# MCU.net
KiCad netlist of a schematic drawn in Altium Designer
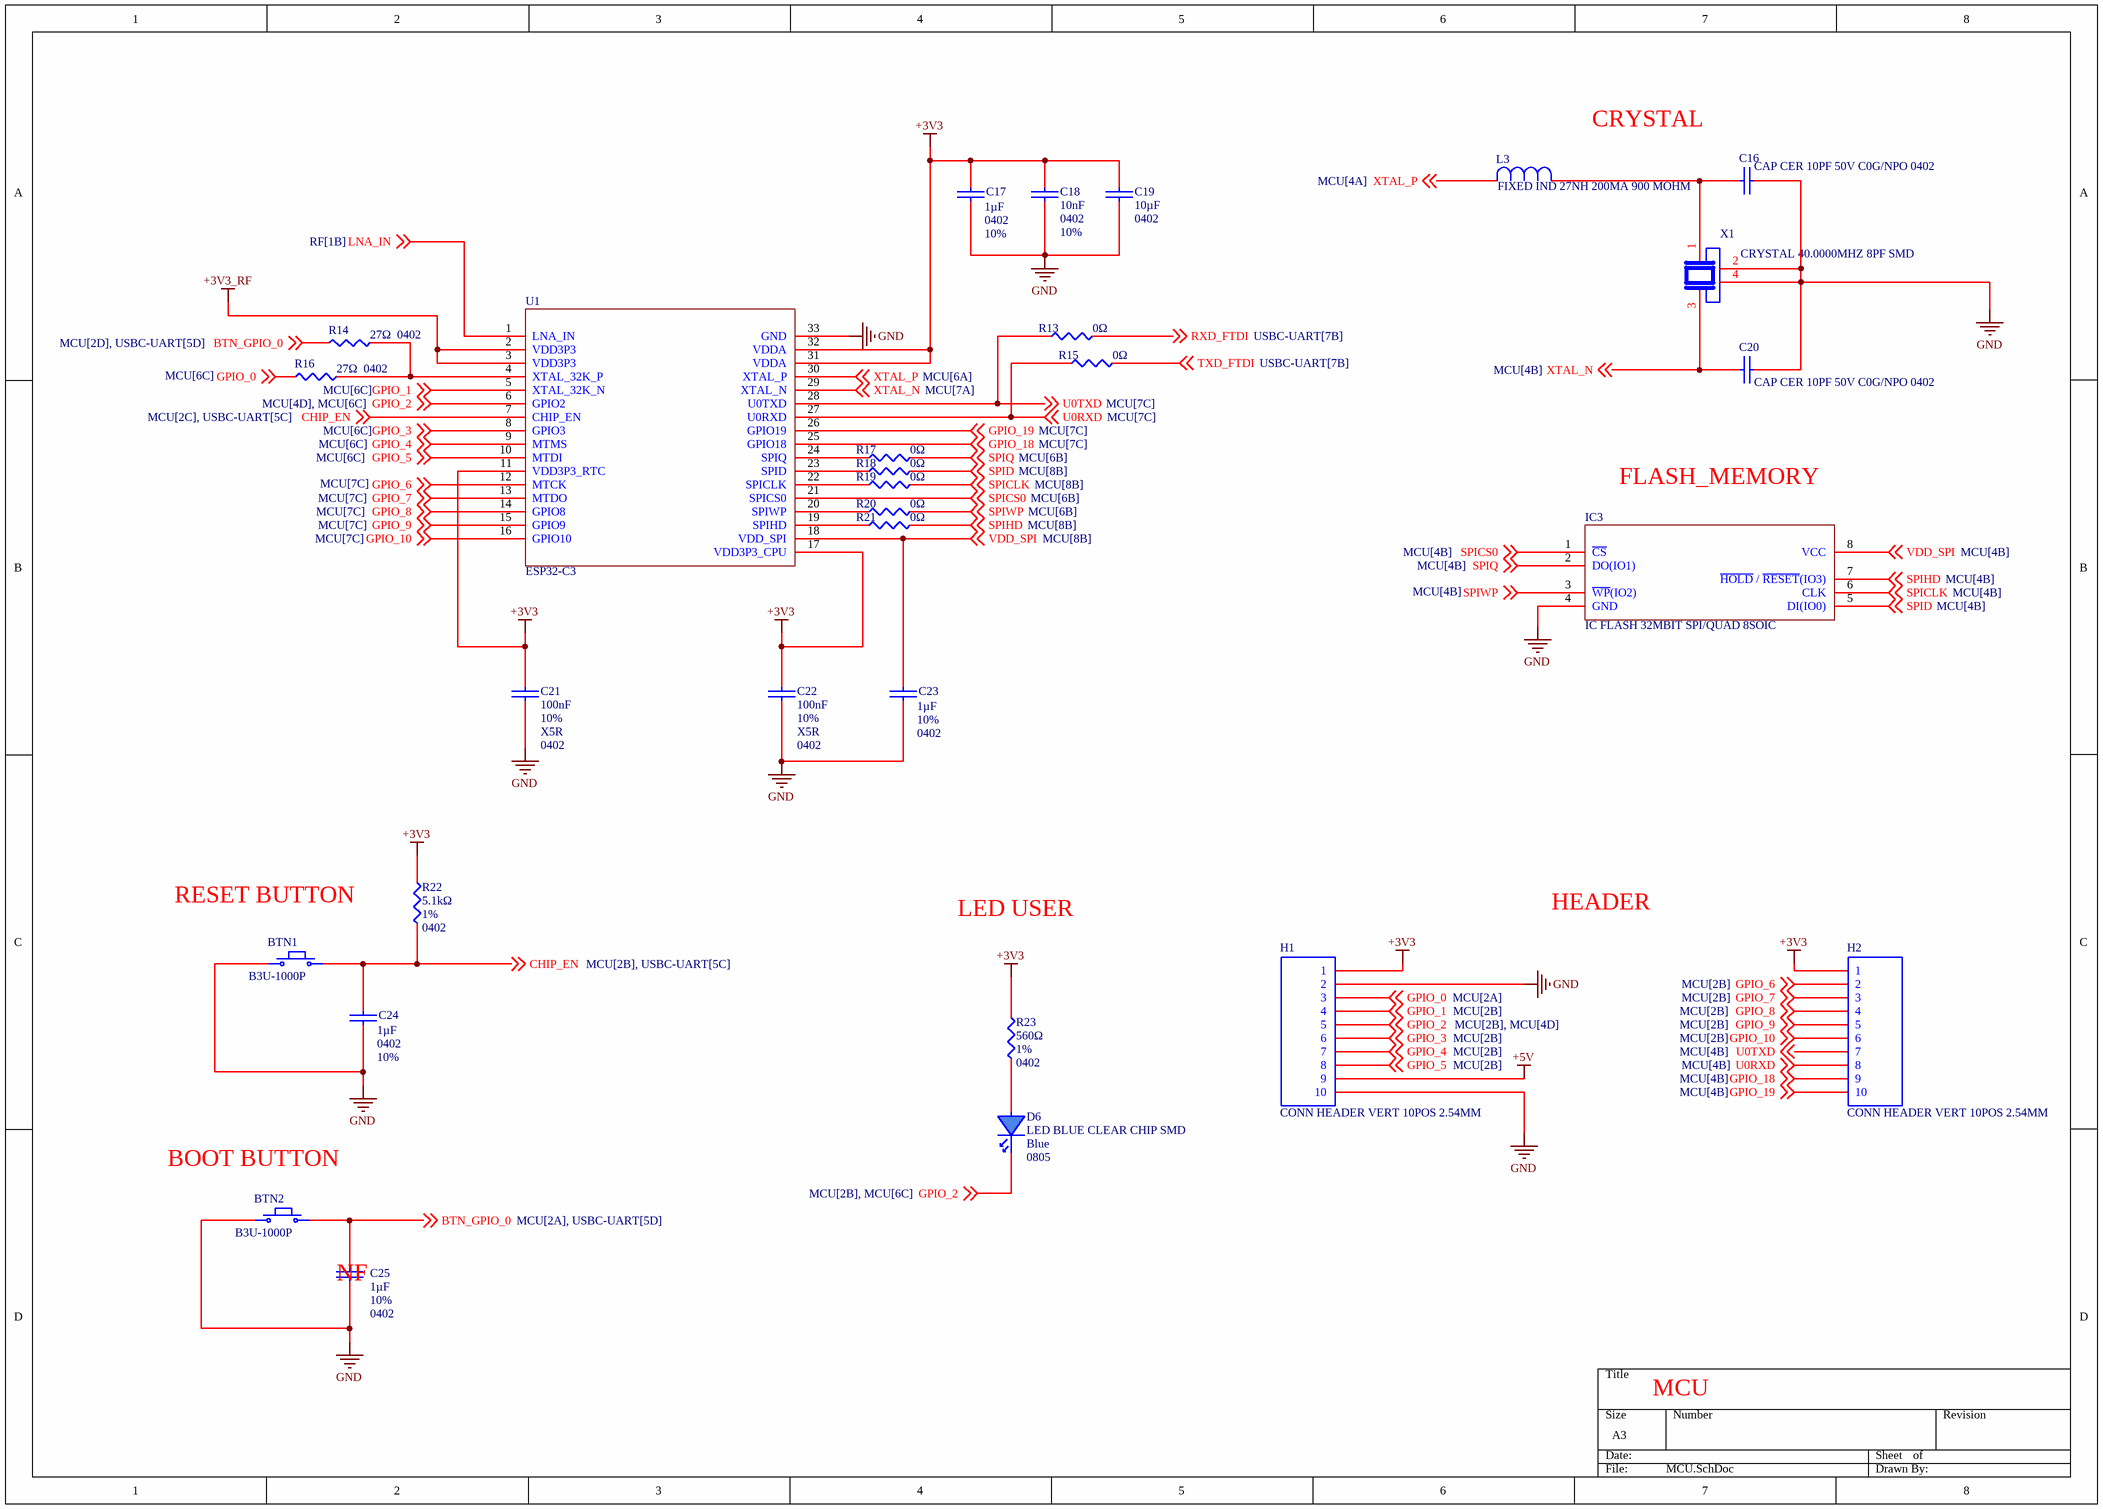
[diagram p0: MCU.SchDoc]

(export (version "E")
  (design (tool "Eeschema 10.0.6"))
  (components
    (comp (ref "BTN1")
      (value "SWITCH TACTILE SPST-NO 0.05A 12V")
      (footprint "SW_B3U-1000P")
      (description "Switch Tactile N.O. SPST Round Button Solder Tab 12VDC 200000Cycles 1.5N SMD Emboss T/R")
      (fields
        (field (name "MANUFACTURER") "Omron")
        (field (name "MANUFACTURER PART NUMBER") "B3U-1000P")
        (field (name "LCSC PART") "C231329")
      )
      (libsource (lib "Schlib") (part "B3U-1000P"))
    )
    (comp (ref "BTN2")
      (value "SWITCH TACTILE SPST-NO 0.05A 12V")
      (footprint "SW_B3U-1000P")
      (description "Switch Tactile N.O. SPST Round Button Solder Tab 12VDC 200000Cycles 1.5N SMD Emboss T/R")
      (fields
        (field (name "MANUFACTURER") "Omron")
        (field (name "MANUFACTURER PART NUMBER") "B3U-1000P")
        (field (name "LCSC PART") "C231329")
      )
      (libsource (lib "Schlib") (part "B3U-1000P"))
    )
    (comp (ref "C16")
      (value "CAP CER 10PF 50V C0G/NPO 0402")
      (footprint "C0402")
      (fields
        (field (name "MANUFACTURER") "Yageo Group")
        (field (name "MANUFACTURER PART NUMBER") "CC0402FPNPO9BN100")
        (field (name "LCSC PART") "C3896396")
      )
      (libsource (lib "Schlib") (part "CC0402FPNPO9BN100"))
    )
    (comp (ref "C17")
      (value "1µF")
      (footprint "C0402")
      (description "Multilayer Ceramic Capacitors MLCC – SMD/SMT; YAGEO; CC0402KRX5R6BB105; 1 µF; 0402; 10 V; 10 V")
      (fields
        (field (name "MANUFACTURER") "Yageo Group")
        (field (name "MANUFACTURER PART NUMBER") "CC0402KRX5R6BB105")
        (field (name "CASE/PACKAGE") "0402")
        (field (name "TOLERANCE") "10%")
      )
      (libsource (lib "Schlib") (part "CC0402KRX5R6BB105"))
    )
    (comp (ref "C18")
      (value "10nF")
      (footprint "C0402")
      (description "Multilayer Ceramic Capacitors MLCC - SMD/SMT 16V 0.01uF X7R 0402 10%")
      (fields
        (field (name "MANUFACTURER") "Yageo Group")
        (field (name "MANUFACTURER PART NUMBER") "CC0402KRX7R7BB103")
        (field (name "CASE/PACKAGE") "0402")
        (field (name "TOLERANCE") "10%")
      )
      (libsource (lib "Schlib") (part "CC0402KRX7R7BB103"))
    )
    (comp (ref "C19")
      (value "10µF")
      (footprint "C0402")
      (description "10V 10uF X5R ±20% 0402 Multilayer Ceramic Capacitors MLCC - SMD/SMT ROHS")
      (fields
        (field (name "MANUFACTURER") "Murata")
        (field (name "MANUFACTURER PART NUMBER") "GRM155R61A106ME11D")
        (field (name "CASE/PACKAGE") "0402")
      )
      (libsource (lib "Schlib") (part "GRM155R61A106ME11D"))
    )
    (comp (ref "C20")
      (value "CAP CER 10PF 50V C0G/NPO 0402")
      (footprint "C0402")
      (fields
        (field (name "MANUFACTURER") "Yageo Group")
        (field (name "MANUFACTURER PART NUMBER") "CC0402FPNPO9BN100")
        (field (name "LCSC PART") "C3896396")
      )
      (libsource (lib "Schlib") (part "CC0402FPNPO9BN100"))
    )
    (comp (ref "C21")
      (value "100nF")
      (footprint "C0402")
      (description "50V 100nF X5R ±10% 0402 Multilayer Ceramic Capacitors MLCC - SMD/SMT ROHS")
      (fields
        (field (name "MANUFACTURER") "Yageo Group")
        (field (name "MANUFACTURER PART NUMBER") "CC0402KRX5R9BB104")
        (field (name "TOLERANCE") "10%")
        (field (name "DIELECTRIC") "X5R")
        (field (name "CASE/PACKAGE") "0402")
      )
      (libsource (lib "Schlib") (part "CC0402KRX5R9BB104"))
    )
    (comp (ref "C22")
      (value "100nF")
      (footprint "C0402")
      (description "50V 100nF X5R ±10% 0402 Multilayer Ceramic Capacitors MLCC - SMD/SMT ROHS")
      (fields
        (field (name "MANUFACTURER") "Yageo Group")
        (field (name "MANUFACTURER PART NUMBER") "CC0402KRX5R9BB104")
        (field (name "TOLERANCE") "10%")
        (field (name "DIELECTRIC") "X5R")
        (field (name "CASE/PACKAGE") "0402")
      )
      (libsource (lib "Schlib") (part "CC0402KRX5R9BB104"))
    )
    (comp (ref "C23")
      (value "1µF")
      (footprint "C0402")
      (description "Multilayer Ceramic Capacitors MLCC – SMD/SMT; YAGEO; CC0402KRX5R6BB105; 1 µF; 0402; 10 V; 10 V")
      (fields
        (field (name "MANUFACTURER") "Yageo Group")
        (field (name "MANUFACTURER PART NUMBER") "CC0402KRX5R6BB105")
        (field (name "CASE/PACKAGE") "0402")
        (field (name "TOLERANCE") "10%")
      )
      (libsource (lib "Schlib") (part "CC0402KRX5R6BB105"))
    )
    (comp (ref "C24")
      (value "1µF")
      (footprint "C0402")
      (description "Multilayer Ceramic Capacitors MLCC – SMD/SMT; YAGEO; CC0402KRX5R6BB105; 1 µF; 0402; 10 V; 10 V")
      (fields
        (field (name "MANUFACTURER") "Yageo Group")
        (field (name "MANUFACTURER PART NUMBER") "CC0402KRX5R6BB105")
        (field (name "CASE/PACKAGE") "0402")
        (field (name "TOLERANCE") "10%")
      )
      (libsource (lib "Schlib") (part "CC0402KRX5R6BB105"))
    )
    (comp (ref "C25")
      (value "1µF")
      (footprint "C0402")
      (description "Multilayer Ceramic Capacitors MLCC – SMD/SMT; YAGEO; CC0402KRX5R6BB105; 1 µF; 0402; 10 V; 10 V")
      (fields
        (field (name "MANUFACTURER") "Yageo Group")
        (field (name "MANUFACTURER PART NUMBER") "CC0402KRX5R6BB105")
        (field (name "CASE/PACKAGE") "0402")
        (field (name "TOLERANCE") "10%")
      )
      (libsource (lib "Schlib") (part "CC0402KRX5R6BB105"))
    )
    (comp (ref "D6")
      (value "LED BLUE CLEAR CHIP SMD")
      (footprint "LED_0805_BLUE")
      (description "LED blue LED0805 wavelength 465~475nm light intensity 28~180mcd vertical sticker")
      (fields
        (field (name "MANUFACTURER") "Diodes Inc.")
        (field (name "MANUFACTURER PART NUMBER") "LTST-C171TBKT")
        (field (name "COLOR") "Blue")
        (field (name "CASE/PACKAGE") "0805")
      )
      (libsource (lib "Schlib") (part "LTST-C171TBKT"))
    )
    (comp (ref "H1")
      (value "CONN HEADER VERT 10POS 2.54MM")
      (footprint "Header 1*10 2.54mm")
      (description "Conn Unshrouded Header HDR 10 POS 2.54mm Solder ST Top Entry Thru-Hole Bag")
      (fields (field (name "MANUFACTURER") "Adam Tech") (field (name "MANUFACTURER PART NUMBER") "PH1-10-UA"))
      (libsource (lib "Schlib") (part "PH1-10-UA"))
    )
    (comp (ref "H2")
      (value "CONN HEADER VERT 10POS 2.54MM")
      (footprint "Header 1*10 2.54mm")
      (description "Conn Unshrouded Header HDR 10 POS 2.54mm Solder ST Top Entry Thru-Hole Bag")
      (fields (field (name "MANUFACTURER") "Adam Tech") (field (name "MANUFACTURER PART NUMBER") "PH1-10-UA"))
      (libsource (lib "Schlib") (part "PH1-10-UA"))
    )
    (comp (ref "IC3")
      (value "IC FLASH 32MBIT SPI/QUAD 8SOIC")
      (footprint "SOIC-8_5P28X5P28_WIN-L")
      (description "NOR Flash Serial (SPI, Dual SPI, Quad SPI) 3V/3.3V 32M-bit 4M x 8 6ns 8-Pin SOIC T/R")
      (fields
        (field (name "MANUFACTURER") "Winbond")
        (field (name "MANUFACTURER PART NUMBER") "W25Q32JVSSIQ TR")
      )
      (libsource (lib "Schlib") (part "W25Q32JVSSIQ TR"))
    )
    (comp (ref "L3")
      (value "FIXED IND 27NH 200MA 900 MOHM")
      (footprint "IND_L-0402_JOT-L")
      (description "General Purpose Inductor, 0.027uH, 5%, 1 Element, Ceramic-Core, SMD, 0402")
      (fields
        (field (name "MANUFACTURER") "Knowles")
        (field (name "MANUFACTURER PART NUMBER") "LRC0402CJ27NGV001T")
      )
      (libsource (lib "Schlib") (part "LRC0402CJ27NGV001T"))
    )
    (comp (ref "R13")
      (value "0Ω")
      (footprint "R0402")
      (description "GENERAL PURPOSE CHIP RESISTOR Metal Glaze/thick Film, 0.0625W, 0ohm, Surface Mount, 0402")
      (fields
        (field (name "MANUFACTURER") "Yageo Group")
        (field (name "MANUFACTURER PART NUMBER") "RC0402JR-070RL")
      )
      (libsource (lib "Schlib") (part "RC0402JR-070RL"))
    )
    (comp (ref "R14")
      (value "27Ω")
      (footprint "R0402")
      (description "62.5mW Thin Film Resistor ±50ppm/℃ ±1% 27Ω 0402 Chip Resistor - Surface Mount ROHS")
      (fields
        (field (name "MANUFACTURER") "Yageo Group")
        (field (name "MANUFACTURER PART NUMBER") "RT0402FRE0727RL")
        (field (name "CASE/PACKAGE") "0402")
      )
      (libsource (lib "Schlib") (part "RT0402FRE0727RL"))
    )
    (comp (ref "R15")
      (value "0Ω")
      (footprint "R0402")
      (description "GENERAL PURPOSE CHIP RESISTOR Metal Glaze/thick Film, 0.0625W, 0ohm, Surface Mount, 0402")
      (fields
        (field (name "MANUFACTURER") "Yageo Group")
        (field (name "MANUFACTURER PART NUMBER") "RC0402JR-070RL")
      )
      (libsource (lib "Schlib") (part "RC0402JR-070RL"))
    )
    (comp (ref "R16")
      (value "27Ω")
      (footprint "R0402")
      (description "62.5mW Thin Film Resistor ±50ppm/℃ ±1% 27Ω 0402 Chip Resistor - Surface Mount ROHS")
      (fields
        (field (name "MANUFACTURER") "Yageo Group")
        (field (name "MANUFACTURER PART NUMBER") "RT0402FRE0727RL")
        (field (name "CASE/PACKAGE") "0402")
      )
      (libsource (lib "Schlib") (part "RT0402FRE0727RL"))
    )
    (comp (ref "R17")
      (value "0Ω")
      (footprint "R0402")
      (description "GENERAL PURPOSE CHIP RESISTOR Metal Glaze/thick Film, 0.0625W, 0ohm, Surface Mount, 0402")
      (fields
        (field (name "MANUFACTURER") "Yageo Group")
        (field (name "MANUFACTURER PART NUMBER") "RC0402JR-070RL")
      )
      (libsource (lib "Schlib") (part "RC0402JR-070RL"))
    )
    (comp (ref "R18")
      (value "0Ω")
      (footprint "R0402")
      (description "GENERAL PURPOSE CHIP RESISTOR Metal Glaze/thick Film, 0.0625W, 0ohm, Surface Mount, 0402")
      (fields
        (field (name "MANUFACTURER") "Yageo Group")
        (field (name "MANUFACTURER PART NUMBER") "RC0402JR-070RL")
      )
      (libsource (lib "Schlib") (part "RC0402JR-070RL"))
    )
    (comp (ref "R19")
      (value "0Ω")
      (footprint "R0402")
      (description "GENERAL PURPOSE CHIP RESISTOR Metal Glaze/thick Film, 0.0625W, 0ohm, Surface Mount, 0402")
      (fields
        (field (name "MANUFACTURER") "Yageo Group")
        (field (name "MANUFACTURER PART NUMBER") "RC0402JR-070RL")
      )
      (libsource (lib "Schlib") (part "RC0402JR-070RL"))
    )
    (comp (ref "R20")
      (value "0Ω")
      (footprint "R0402")
      (description "GENERAL PURPOSE CHIP RESISTOR Metal Glaze/thick Film, 0.0625W, 0ohm, Surface Mount, 0402")
      (fields
        (field (name "MANUFACTURER") "Yageo Group")
        (field (name "MANUFACTURER PART NUMBER") "RC0402JR-070RL")
      )
      (libsource (lib "Schlib") (part "RC0402JR-070RL"))
    )
    (comp (ref "R21")
      (value "0Ω")
      (footprint "R0402")
      (description "GENERAL PURPOSE CHIP RESISTOR Metal Glaze/thick Film, 0.0625W, 0ohm, Surface Mount, 0402")
      (fields
        (field (name "MANUFACTURER") "Yageo Group")
        (field (name "MANUFACTURER PART NUMBER") "RC0402JR-070RL")
      )
      (libsource (lib "Schlib") (part "RC0402JR-070RL"))
    )
    (comp (ref "R22")
      (value "5.1kΩ")
      (footprint "R0402")
      (description "62.5mW Thick Film Resistors 50V ±100ppm/℃ ±1% 5.1kΩ 0402 Chip Resistor - Surface Mount ROHS")
      (fields
        (field (name "MANUFACTURER") "Yageo Group")
        (field (name "MANUFACTURER PART NUMBER") "RC0402FR-075K1L")
        (field (name "TOLERANCE") "1%")
        (field (name "CASE/PACKAGE") "0402")
      )
      (libsource (lib "Schlib") (part "RC0402FR-075K1L"))
    )
    (comp (ref "R23")
      (value "560Ω")
      (footprint "R0402")
      (description "RC Series 0402 0.063 W 560 Ohm ±1% ±100 ppm/°C SMT Thick Film Chip Resistor")
      (fields
        (field (name "MANUFACTURER") "Yageo Group")
        (field (name "MANUFACTURER PART NUMBER") "RC0402FR-13560RL")
        (field (name "TOLERANCE") "1%")
        (field (name "CASE/PACKAGE") "0402")
      )
      (libsource (lib "Schlib") (part "RC0402FR-13560RL"))
    )
    (comp (ref "U1")
      (value "ESP32-C3")
      (footprint "ESP-C3")
      (description "400KB 22 3V~3.6V RISC-V 160MHz QFN-32-EP(5x5) Microcontroller Units (MCUs/MPUs/SOCs) ROHS")
      (fields (field (name "MANUFACTURER") "Espressif Systems") (field (name "LCSC PART") "C2838500"))
      (libsource (lib "Schlib") (part "ESP32-C3"))
    )
    (comp (ref "X1")
      (value "CRYSTAL 40.0000MHZ 8PF SMD")
      (footprint "OSC_XRCGB40M000F1S1BR0")
      (description "Crystal 40MHz ±10ppm (Tol) ±10ppm (Stability) 8pF 50Ohm 4-Pin CSMD T/R")
      (fields
        (field (name "MANUFACTURER") "Murata")
        (field (name "MANUFACTURER PART NUMBER") "XRCGB40M000F1S1BR0")
      )
      (libsource (lib "Schlib") (part "XRCGB40M000F1S1BR0"))
    )
  )
  (nets
    (net (code "1") (name "+3V3") (class "Default")
      (node (ref "C17") (pin "1") (pinfunction "1_1") (pintype "passive"))
      (node (ref "C18") (pin "2") (pinfunction "2_2") (pintype "passive"))
      (node (ref "C19") (pin "2") (pinfunction "2_2") (pintype "passive"))
      (node (ref "C21") (pin "2") (pinfunction "2_2") (pintype "passive"))
      (node (ref "C22") (pin "2") (pinfunction "2_2") (pintype "passive"))
      (node (ref "H1") (pin "1") (pinfunction "1_1") (pintype "passive"))
      (node (ref "H2") (pin "1") (pinfunction "1_1") (pintype "passive"))
      (node (ref "R22") (pin "2") (pinfunction "2_2") (pintype "passive"))
      (node (ref "R23") (pin "2") (pinfunction "2_2") (pintype "passive"))
      (node (ref "U1") (pin "11") (pinfunction "VDD3P3_RTC_11") (pintype "passive"))
      (node (ref "U1") (pin "17") (pinfunction "VDD3P3_CPU_17") (pintype "passive"))
      (node (ref "U1") (pin "31") (pinfunction "VDDA_31") (pintype "passive"))
      (node (ref "U1") (pin "32") (pinfunction "VDDA_32") (pintype "passive"))
    )
    (net (code "2") (name "+3V3_RF") (class "Default")
      (node (ref "U1") (pin "2") (pinfunction "VDD3P3_2") (pintype "passive"))
      (node (ref "U1") (pin "3") (pinfunction "VDD3P3_3") (pintype "passive"))
    )
    (net (code "3") (name "+5V") (class "Default")
      (node (ref "H1") (pin "9") (pinfunction "9_9") (pintype "passive"))
    )
    (net (code "4") (name "BTN_GPIO_0") (class "Default")
      (node (ref "BTN2") (pin "2") (pinfunction "2_2") (pintype "passive"))
      (node (ref "C25") (pin "2") (pinfunction "2_2") (pintype "passive"))
      (node (ref "R14") (pin "1") (pinfunction "1_1") (pintype "passive"))
    )
    (net (code "5") (name "CHIP_EN") (class "Default")
      (node (ref "BTN1") (pin "2") (pinfunction "2_2") (pintype "passive"))
      (node (ref "C24") (pin "2") (pinfunction "2_2") (pintype "passive"))
      (node (ref "R22") (pin "1") (pinfunction "1_1") (pintype "passive"))
      (node (ref "U1") (pin "7") (pinfunction "CHIP_EN_7") (pintype "passive"))
    )
    (net (code "6") (name "GND") (class "Default")
      (node (ref "BTN1") (pin "1") (pinfunction "1_1") (pintype "passive"))
      (node (ref "BTN2") (pin "1") (pinfunction "1_1") (pintype "passive"))
      (node (ref "C16") (pin "1") (pinfunction "1_1") (pintype "passive"))
      (node (ref "C17") (pin "2") (pinfunction "2_2") (pintype "passive"))
      (node (ref "C18") (pin "1") (pinfunction "1_1") (pintype "passive"))
      (node (ref "C19") (pin "1") (pinfunction "1_1") (pintype "passive"))
      (node (ref "C20") (pin "1") (pinfunction "1_1") (pintype "passive"))
      (node (ref "C21") (pin "1") (pinfunction "1_1") (pintype "passive"))
      (node (ref "C22") (pin "1") (pinfunction "1_1") (pintype "passive"))
      (node (ref "C23") (pin "1") (pinfunction "1_1") (pintype "passive"))
      (node (ref "C24") (pin "1") (pinfunction "1_1") (pintype "passive"))
      (node (ref "C25") (pin "1") (pinfunction "1_1") (pintype "passive"))
      (node (ref "H1") (pin "10") (pinfunction "10_10") (pintype "passive"))
      (node (ref "H1") (pin "2") (pinfunction "2_2") (pintype "passive"))
      (node (ref "IC3") (pin "4") (pinfunction "GND_4") (pintype "power_in"))
      (node (ref "U1") (pin "33") (pinfunction "GND_33") (pintype "passive"))
      (node (ref "X1") (pin "2") (pinfunction "2_2") (pintype "passive"))
      (node (ref "X1") (pin "4") (pinfunction "4_4") (pintype "passive"))
    )
    (net (code "7") (name "GPIO_0") (class "Default")
      (node (ref "H1") (pin "3") (pinfunction "3_3") (pintype "passive"))
      (node (ref "R16") (pin "1") (pinfunction "1_1") (pintype "passive"))
    )
    (net (code "8") (name "GPIO_1") (class "Default")
      (node (ref "H1") (pin "4") (pinfunction "4_4") (pintype "passive"))
      (node (ref "U1") (pin "5") (pinfunction "XTAL_32K_N_5") (pintype "passive"))
    )
    (net (code "9") (name "GPIO_2") (class "Default")
      (node (ref "D6") (pin "1") (pinfunction "1_1") (pintype "passive"))
      (node (ref "H1") (pin "5") (pinfunction "5_5") (pintype "passive"))
      (node (ref "U1") (pin "6") (pinfunction "GPIO2_6") (pintype "passive"))
    )
    (net (code "10") (name "GPIO_3") (class "Default")
      (node (ref "H1") (pin "6") (pinfunction "6_6") (pintype "passive"))
      (node (ref "U1") (pin "8") (pinfunction "GPIO3_8") (pintype "passive"))
    )
    (net (code "11") (name "GPIO_4") (class "Default")
      (node (ref "H1") (pin "7") (pinfunction "7_7") (pintype "passive"))
      (node (ref "U1") (pin "9") (pinfunction "MTMS_9") (pintype "passive"))
    )
    (net (code "12") (name "GPIO_5") (class "Default")
      (node (ref "H1") (pin "8") (pinfunction "8_8") (pintype "passive"))
      (node (ref "U1") (pin "10") (pinfunction "MTDI_10") (pintype "passive"))
    )
    (net (code "13") (name "GPIO_6") (class "Default")
      (node (ref "H2") (pin "2") (pinfunction "2_2") (pintype "passive"))
      (node (ref "U1") (pin "12") (pinfunction "MTCK_12") (pintype "passive"))
    )
    (net (code "14") (name "GPIO_7") (class "Default")
      (node (ref "H2") (pin "3") (pinfunction "3_3") (pintype "passive"))
      (node (ref "U1") (pin "13") (pinfunction "MTDO_13") (pintype "passive"))
    )
    (net (code "15") (name "GPIO_8") (class "Default")
      (node (ref "H2") (pin "4") (pinfunction "4_4") (pintype "passive"))
      (node (ref "U1") (pin "14") (pinfunction "GPIO8_14") (pintype "passive"))
    )
    (net (code "16") (name "GPIO_9") (class "Default")
      (node (ref "H2") (pin "5") (pinfunction "5_5") (pintype "passive"))
      (node (ref "U1") (pin "15") (pinfunction "GPIO9_15") (pintype "passive"))
    )
    (net (code "17") (name "GPIO_10") (class "Default")
      (node (ref "H2") (pin "6") (pinfunction "6_6") (pintype "passive"))
      (node (ref "U1") (pin "16") (pinfunction "GPIO10_16") (pintype "passive"))
    )
    (net (code "18") (name "GPIO_18") (class "Default")
      (node (ref "H2") (pin "9") (pinfunction "9_9") (pintype "passive"))
      (node (ref "U1") (pin "25") (pinfunction "GPIO18_25") (pintype "passive"))
    )
    (net (code "19") (name "GPIO_19") (class "Default")
      (node (ref "H2") (pin "10") (pinfunction "10_10") (pintype "passive"))
      (node (ref "U1") (pin "26") (pinfunction "GPIO19_26") (pintype "passive"))
    )
    (net (code "20") (name "LNA_IN") (class "Default")
      (node (ref "U1") (pin "1") (pinfunction "LNA_IN_1") (pintype "passive"))
    )
    (net (code "21") (name "Net-(C16-Pad2)") (class "Default")
      (node (ref "C16") (pin "2") (pinfunction "2_2") (pintype "passive"))
      (node (ref "L3") (pin "1") (pinfunction "1_1") (pintype "passive"))
      (node (ref "X1") (pin "1") (pinfunction "1_1") (pintype "passive"))
    )
    (net (code "22") (name "Net-(D6-Pad2)") (class "Default")
      (node (ref "D6") (pin "2") (pinfunction "2_2") (pintype "passive"))
      (node (ref "R23") (pin "1") (pinfunction "1_1") (pintype "passive"))
    )
    (net (code "23") (name "Net-(U1-SPICLK)") (class "Default")
      (node (ref "R19") (pin "1") (pinfunction "1_1") (pintype "passive"))
      (node (ref "U1") (pin "22") (pinfunction "SPICLK_22") (pintype "passive"))
    )
    (net (code "24") (name "Net-(U1-SPID)") (class "Default")
      (node (ref "R18") (pin "1") (pinfunction "1_1") (pintype "passive"))
      (node (ref "U1") (pin "23") (pinfunction "SPID_23") (pintype "passive"))
    )
    (net (code "25") (name "Net-(U1-SPIHD)") (class "Default")
      (node (ref "R21") (pin "1") (pinfunction "1_1") (pintype "passive"))
      (node (ref "U1") (pin "19") (pinfunction "SPIHD_19") (pintype "passive"))
    )
    (net (code "26") (name "Net-(U1-SPIQ)") (class "Default")
      (node (ref "R17") (pin "1") (pinfunction "1_1") (pintype "passive"))
      (node (ref "U1") (pin "24") (pinfunction "SPIQ_24") (pintype "passive"))
    )
    (net (code "27") (name "Net-(U1-SPIWP)") (class "Default")
      (node (ref "R20") (pin "1") (pinfunction "1_1") (pintype "passive"))
      (node (ref "U1") (pin "20") (pinfunction "SPIWP_20") (pintype "passive"))
    )
    (net (code "28") (name "Net-(U1-XTAL_32K_P)") (class "Default")
      (node (ref "R14") (pin "2") (pinfunction "2_2") (pintype "passive"))
      (node (ref "R16") (pin "2") (pinfunction "2_2") (pintype "passive"))
      (node (ref "U1") (pin "4") (pinfunction "XTAL_32K_P_4") (pintype "passive"))
    )
    (net (code "29") (name "RXD_FTDI") (class "Default")
      (node (ref "R13") (pin "2") (pinfunction "2_2") (pintype "passive"))
    )
    (net (code "30") (name "SPICLK") (class "Default")
      (node (ref "IC3") (pin "6") (pinfunction "CLK_6") (pintype "passive"))
      (node (ref "R19") (pin "2") (pinfunction "2_2") (pintype "passive"))
    )
    (net (code "31") (name "SPICS0") (class "Default")
      (node (ref "IC3") (pin "1") (pinfunction "~{CS}_1") (pintype "passive"))
      (node (ref "U1") (pin "21") (pinfunction "SPICS0_21") (pintype "passive"))
    )
    (net (code "32") (name "SPID") (class "Default")
      (node (ref "IC3") (pin "5") (pinfunction "DI(IO0)_5") (pintype "passive"))
      (node (ref "R18") (pin "2") (pinfunction "2_2") (pintype "passive"))
    )
    (net (code "33") (name "SPIHD") (class "Default")
      (node (ref "IC3") (pin "7") (pinfunction "~{HOLD}_/_~{RESET}(IO3)_7") (pintype "passive"))
      (node (ref "R21") (pin "2") (pinfunction "2_2") (pintype "passive"))
    )
    (net (code "34") (name "SPIQ") (class "Default")
      (node (ref "IC3") (pin "2") (pinfunction "DO(IO1)_2") (pintype "passive"))
      (node (ref "R17") (pin "2") (pinfunction "2_2") (pintype "passive"))
    )
    (net (code "35") (name "SPIWP") (class "Default")
      (node (ref "IC3") (pin "3") (pinfunction "~{WP}(IO2)_3") (pintype "passive"))
      (node (ref "R20") (pin "2") (pinfunction "2_2") (pintype "passive"))
    )
    (net (code "36") (name "TXD_FTDI") (class "Default")
      (node (ref "R15") (pin "2") (pinfunction "2_2") (pintype "passive"))
    )
    (net (code "37") (name "U0RXD") (class "Default")
      (node (ref "H2") (pin "8") (pinfunction "8_8") (pintype "passive"))
      (node (ref "R15") (pin "1") (pinfunction "1_1") (pintype "passive"))
      (node (ref "U1") (pin "27") (pinfunction "U0RXD_27") (pintype "passive"))
    )
    (net (code "38") (name "U0TXD") (class "Default")
      (node (ref "H2") (pin "7") (pinfunction "7_7") (pintype "passive"))
      (node (ref "R13") (pin "1") (pinfunction "1_1") (pintype "passive"))
      (node (ref "U1") (pin "28") (pinfunction "U0TXD_28") (pintype "passive"))
    )
    (net (code "39") (name "VDD_SPI") (class "Default")
      (node (ref "C23") (pin "2") (pinfunction "2_2") (pintype "passive"))
      (node (ref "IC3") (pin "8") (pinfunction "VCC_8") (pintype "power_in"))
      (node (ref "U1") (pin "18") (pinfunction "VDD_SPI_18") (pintype "passive"))
    )
    (net (code "40") (name "XTAL_N") (class "Default")
      (node (ref "C20") (pin "2") (pinfunction "2_2") (pintype "passive"))
      (node (ref "U1") (pin "29") (pinfunction "XTAL_N_29") (pintype "passive"))
      (node (ref "X1") (pin "3") (pinfunction "3_3") (pintype "passive"))
    )
    (net (code "41") (name "XTAL_P") (class "Default")
      (node (ref "L3") (pin "2") (pinfunction "2_2") (pintype "passive"))
      (node (ref "U1") (pin "30") (pinfunction "XTAL_P_30") (pintype "passive"))
    )
  )
)
